# pck100clone.net
KiCad netlist of a schematic drawn in EAGLE
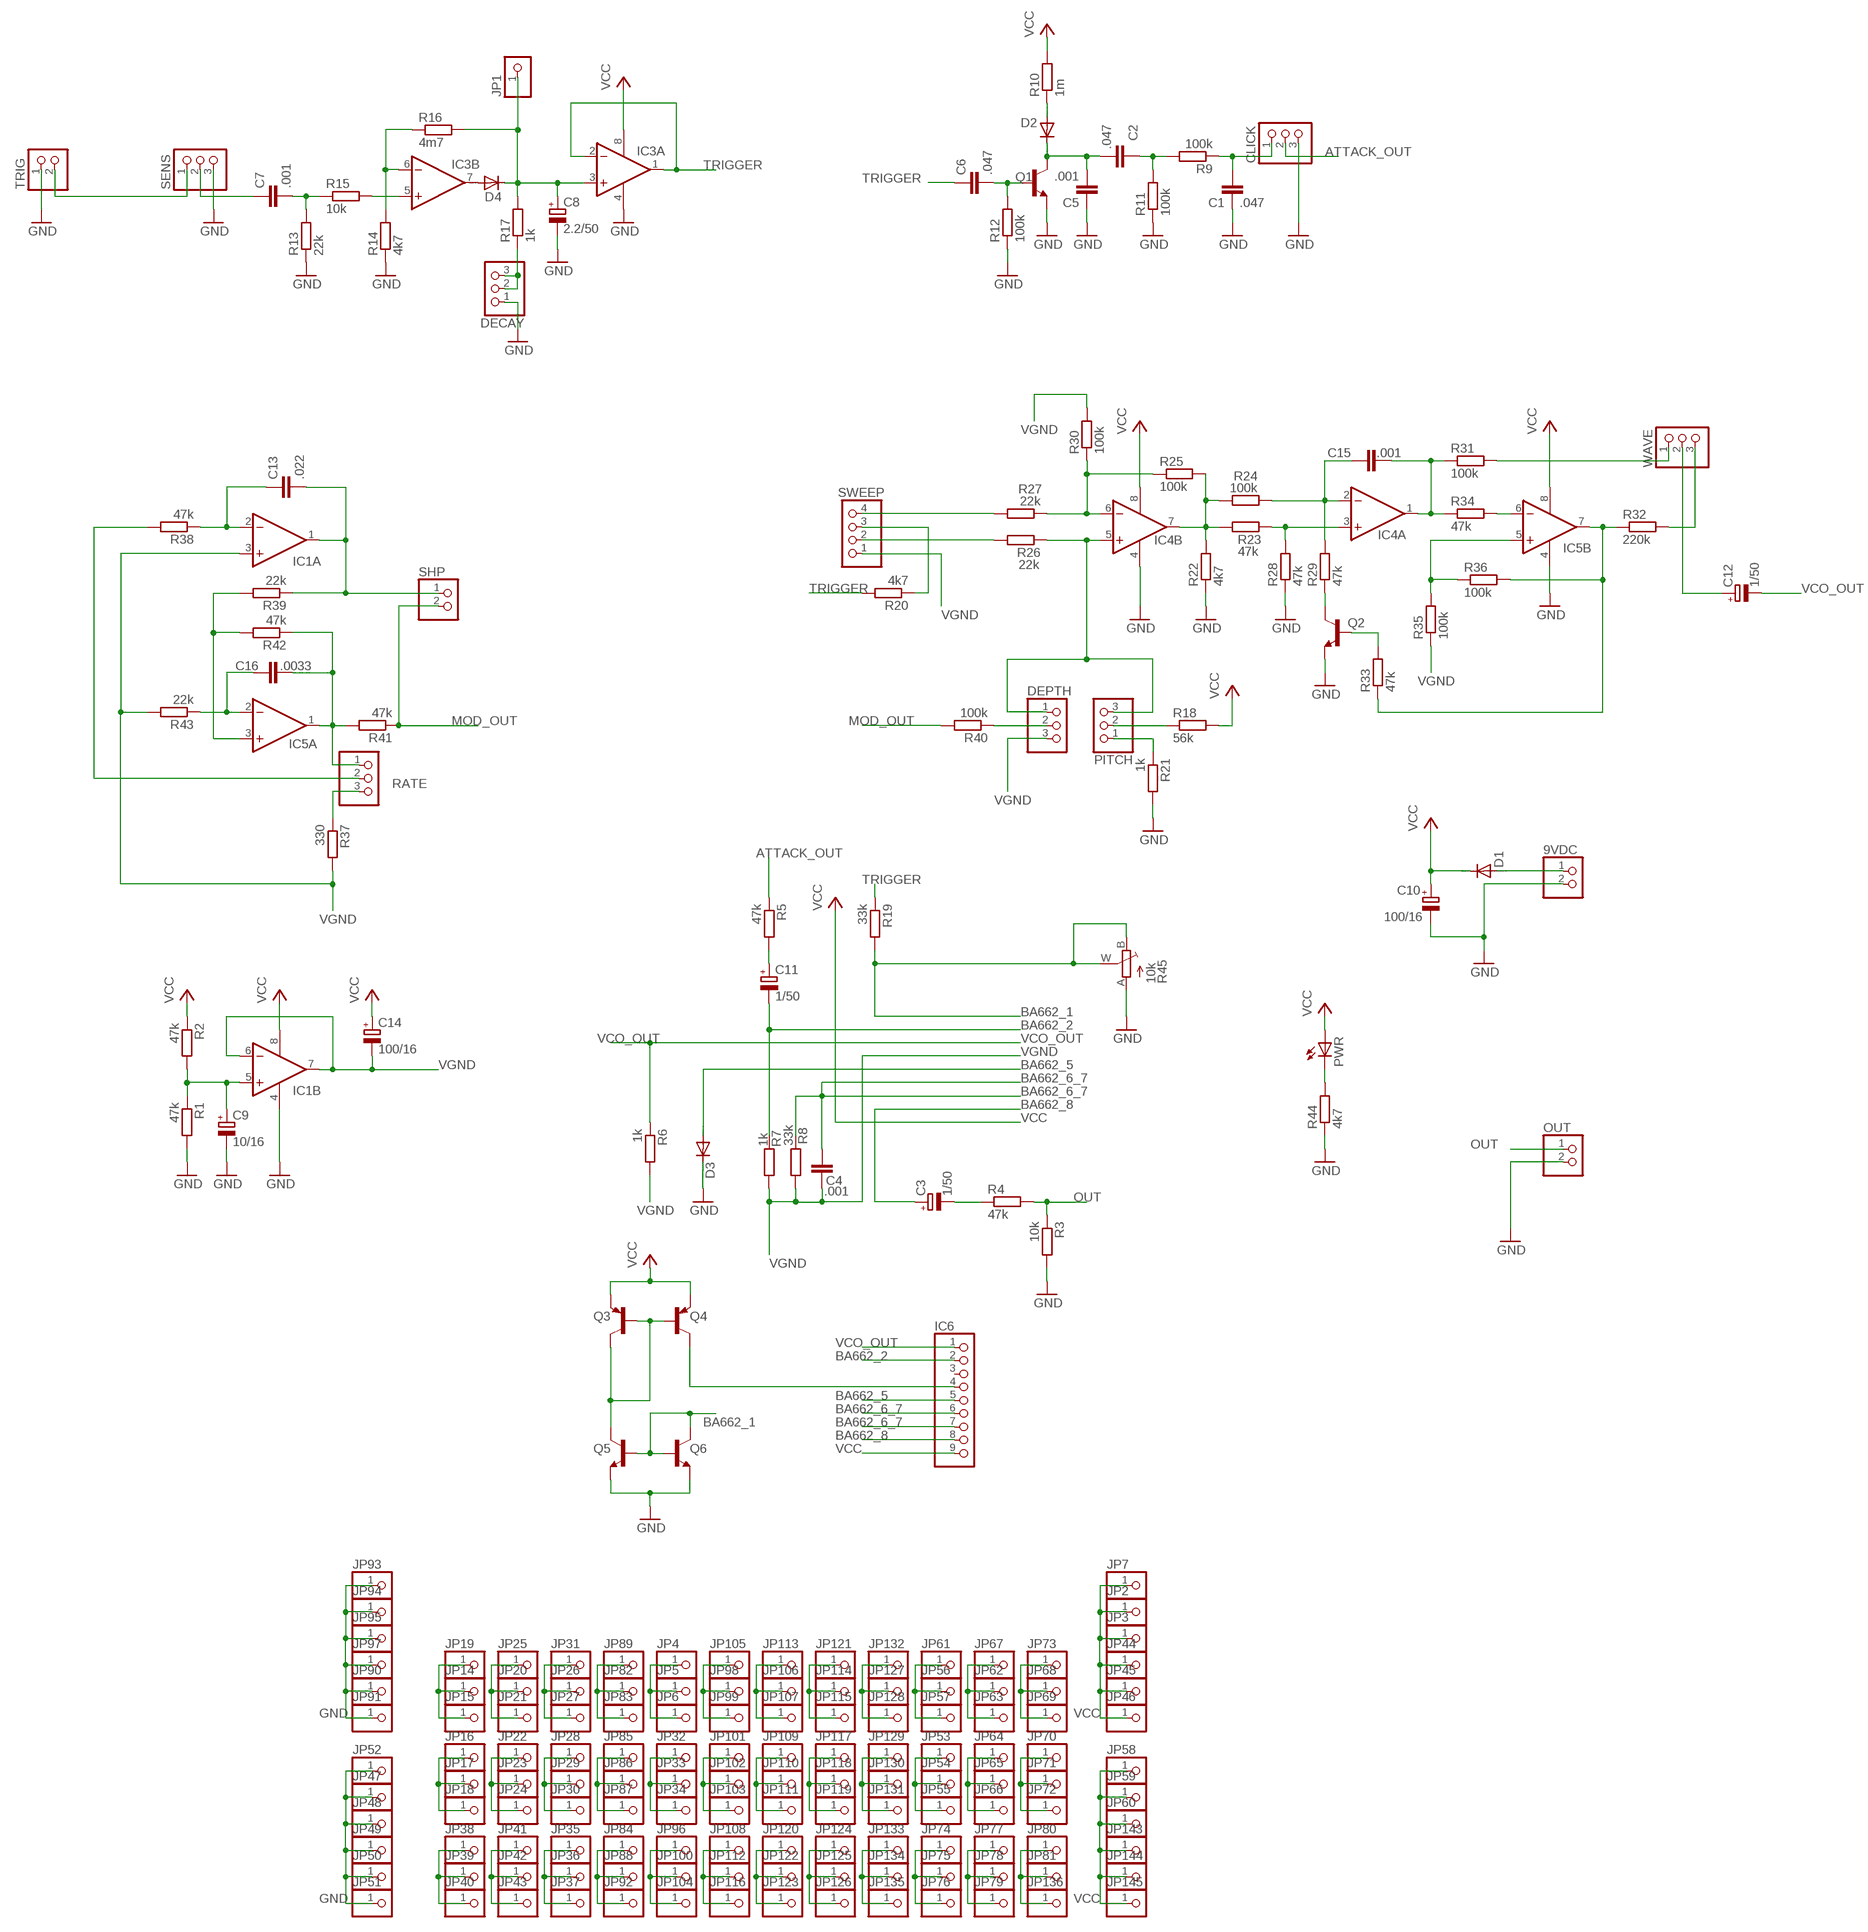
[diagram p0: schematic, sheet 1]

(export (version "E")
  (design (tool "Eeschema 10.0.6"))
  (components
    (comp (ref "9VDC")
      (value "PINHD-1X2")
      (footprint "eagle-import:1X02")
      (libsource (lib "eagle-import") (part "PINHD-1X2"))
    )
    (comp (ref "C1")
      (value ".047")
      (footprint "eagle-import:C050-025X075")
      (libsource (lib "eagle-import") (part "C-EU050-025X075"))
    )
    (comp (ref "C2")
      (value ".047")
      (footprint "eagle-import:C050-025X075")
      (libsource (lib "eagle-import") (part "C-EU050-025X075"))
    )
    (comp (ref "C3")
      (value "1/50")
      (footprint "eagle-import:E2,5-5")
      (libsource (lib "eagle-import") (part "CPOL-EUE2.5-5"))
    )
    (comp (ref "C4")
      (value ".001")
      (footprint "eagle-import:C050-025X075")
      (libsource (lib "eagle-import") (part "C-EU050-025X075"))
    )
    (comp (ref "C5")
      (value ".001")
      (footprint "eagle-import:C050-025X075")
      (libsource (lib "eagle-import") (part "C-EU050-025X075"))
    )
    (comp (ref "C6")
      (value ".047")
      (footprint "eagle-import:C050-025X075")
      (libsource (lib "eagle-import") (part "C-EU050-025X075"))
    )
    (comp (ref "C7")
      (value ".001")
      (footprint "eagle-import:C050-025X075")
      (libsource (lib "eagle-import") (part "C-EU050-025X075"))
    )
    (comp (ref "C8")
      (value "2.2/50")
      (footprint "eagle-import:E2,5-5")
      (libsource (lib "eagle-import") (part "CPOL-EUE2.5-5"))
    )
    (comp (ref "C9")
      (value "10/16")
      (footprint "eagle-import:E2,5-5")
      (libsource (lib "eagle-import") (part "CPOL-EUE2.5-5"))
    )
    (comp (ref "C10")
      (value "100/16")
      (footprint "eagle-import:E2,5-5")
      (libsource (lib "eagle-import") (part "CPOL-EUE2.5-5"))
    )
    (comp (ref "C11")
      (value "1/50")
      (footprint "eagle-import:E2,5-5")
      (libsource (lib "eagle-import") (part "CPOL-EUE2.5-5"))
    )
    (comp (ref "C12")
      (value "1/50")
      (footprint "eagle-import:E2,5-5")
      (libsource (lib "eagle-import") (part "CPOL-EUE2.5-5"))
    )
    (comp (ref "C13")
      (value ".022")
      (footprint "eagle-import:C050-025X075")
      (libsource (lib "eagle-import") (part "C-EU050-025X075"))
    )
    (comp (ref "C14")
      (value "100/16")
      (footprint "eagle-import:E2,5-5")
      (libsource (lib "eagle-import") (part "CPOL-EUE2.5-5"))
    )
    (comp (ref "C15")
      (value ".001")
      (footprint "eagle-import:C050-025X075")
      (libsource (lib "eagle-import") (part "C-EU050-025X075"))
    )
    (comp (ref "C16")
      (value ".0033")
      (footprint "eagle-import:C050-025X075")
      (libsource (lib "eagle-import") (part "C-EU050-025X075"))
    )
    (comp (ref "CLICK")
      (value "PINHD-1X3")
      (footprint "eagle-import:1X03")
      (libsource (lib "eagle-import") (part "PINHD-1X3"))
    )
    (comp (ref "D1")
      (value "1N4004")
      (footprint "eagle-import:DO41-10")
      (libsource (lib "eagle-import") (part "1N4004"))
    )
    (comp (ref "D2")
      (value "1N4148DO35-7")
      (footprint "eagle-import:DO35-7")
      (libsource (lib "eagle-import") (part "1N4148DO35-7"))
    )
    (comp (ref "D3")
      (value "1N4148DO35-7")
      (footprint "eagle-import:DO35-7")
      (libsource (lib "eagle-import") (part "1N4148DO35-7"))
    )
    (comp (ref "D4")
      (value "1N4148DO35-7")
      (footprint "eagle-import:DO35-7")
      (libsource (lib "eagle-import") (part "1N4148DO35-7"))
    )
    (comp (ref "DECAY")
      (value "PINHD-1X3")
      (footprint "eagle-import:1X03")
      (libsource (lib "eagle-import") (part "PINHD-1X3"))
    )
    (comp (ref "DEPTH")
      (value "PINHD-1X3")
      (footprint "eagle-import:1X03")
      (libsource (lib "eagle-import") (part "PINHD-1X3"))
    )
    (comp (ref "IC1")
      (value "LM358N")
      (footprint "eagle-import:DIL08")
      (libsource (lib "eagle-import") (part "LM358N"))
    )
    (comp (ref "IC3")
      (value "LM358N")
      (footprint "eagle-import:DIL08")
      (libsource (lib "eagle-import") (part "LM358N"))
    )
    (comp (ref "IC4")
      (value "LM358N")
      (footprint "eagle-import:DIL08")
      (libsource (lib "eagle-import") (part "LM358N"))
    )
    (comp (ref "IC5")
      (value "LM358N")
      (footprint "eagle-import:DIL08")
      (libsource (lib "eagle-import") (part "LM358N"))
    )
    (comp (ref "IC6")
      (value "PINHD-1X9")
      (footprint "eagle-import:1X09")
      (libsource (lib "eagle-import") (part "PINHD-1X9"))
    )
    (comp (ref "JP1")
      (value "PINHD-1X1")
      (footprint "eagle-import:1X01")
      (libsource (lib "eagle-import") (part "PINHD-1X1"))
    )
    (comp (ref "JP2")
      (value "PINHD-1X1")
      (footprint "eagle-import:1X01")
      (libsource (lib "eagle-import") (part "PINHD-1X1"))
    )
    (comp (ref "JP3")
      (value "PINHD-1X1")
      (footprint "eagle-import:1X01")
      (libsource (lib "eagle-import") (part "PINHD-1X1"))
    )
    (comp (ref "JP4")
      (value "PINHD-1X1")
      (footprint "eagle-import:1X01")
      (libsource (lib "eagle-import") (part "PINHD-1X1"))
    )
    (comp (ref "JP5")
      (value "PINHD-1X1")
      (footprint "eagle-import:1X01")
      (libsource (lib "eagle-import") (part "PINHD-1X1"))
    )
    (comp (ref "JP6")
      (value "PINHD-1X1")
      (footprint "eagle-import:1X01")
      (libsource (lib "eagle-import") (part "PINHD-1X1"))
    )
    (comp (ref "JP7")
      (value "PINHD-1X1")
      (footprint "eagle-import:1X01")
      (libsource (lib "eagle-import") (part "PINHD-1X1"))
    )
    (comp (ref "JP14")
      (value "PINHD-1X1")
      (footprint "eagle-import:1X01")
      (libsource (lib "eagle-import") (part "PINHD-1X1"))
    )
    (comp (ref "JP15")
      (value "PINHD-1X1")
      (footprint "eagle-import:1X01")
      (libsource (lib "eagle-import") (part "PINHD-1X1"))
    )
    (comp (ref "JP16")
      (value "PINHD-1X1")
      (footprint "eagle-import:1X01")
      (libsource (lib "eagle-import") (part "PINHD-1X1"))
    )
    (comp (ref "JP17")
      (value "PINHD-1X1")
      (footprint "eagle-import:1X01")
      (libsource (lib "eagle-import") (part "PINHD-1X1"))
    )
    (comp (ref "JP18")
      (value "PINHD-1X1")
      (footprint "eagle-import:1X01")
      (libsource (lib "eagle-import") (part "PINHD-1X1"))
    )
    (comp (ref "JP19")
      (value "PINHD-1X1")
      (footprint "eagle-import:1X01")
      (libsource (lib "eagle-import") (part "PINHD-1X1"))
    )
    (comp (ref "JP20")
      (value "PINHD-1X1")
      (footprint "eagle-import:1X01")
      (libsource (lib "eagle-import") (part "PINHD-1X1"))
    )
    (comp (ref "JP21")
      (value "PINHD-1X1")
      (footprint "eagle-import:1X01")
      (libsource (lib "eagle-import") (part "PINHD-1X1"))
    )
    (comp (ref "JP22")
      (value "PINHD-1X1")
      (footprint "eagle-import:1X01")
      (libsource (lib "eagle-import") (part "PINHD-1X1"))
    )
    (comp (ref "JP23")
      (value "PINHD-1X1")
      (footprint "eagle-import:1X01")
      (libsource (lib "eagle-import") (part "PINHD-1X1"))
    )
    (comp (ref "JP24")
      (value "PINHD-1X1")
      (footprint "eagle-import:1X01")
      (libsource (lib "eagle-import") (part "PINHD-1X1"))
    )
    (comp (ref "JP25")
      (value "PINHD-1X1")
      (footprint "eagle-import:1X01")
      (libsource (lib "eagle-import") (part "PINHD-1X1"))
    )
    (comp (ref "JP26")
      (value "PINHD-1X1")
      (footprint "eagle-import:1X01")
      (libsource (lib "eagle-import") (part "PINHD-1X1"))
    )
    (comp (ref "JP27")
      (value "PINHD-1X1")
      (footprint "eagle-import:1X01")
      (libsource (lib "eagle-import") (part "PINHD-1X1"))
    )
    (comp (ref "JP28")
      (value "PINHD-1X1")
      (footprint "eagle-import:1X01")
      (libsource (lib "eagle-import") (part "PINHD-1X1"))
    )
    (comp (ref "JP29")
      (value "PINHD-1X1")
      (footprint "eagle-import:1X01")
      (libsource (lib "eagle-import") (part "PINHD-1X1"))
    )
    (comp (ref "JP30")
      (value "PINHD-1X1")
      (footprint "eagle-import:1X01")
      (libsource (lib "eagle-import") (part "PINHD-1X1"))
    )
    (comp (ref "JP31")
      (value "PINHD-1X1")
      (footprint "eagle-import:1X01")
      (libsource (lib "eagle-import") (part "PINHD-1X1"))
    )
    (comp (ref "JP32")
      (value "PINHD-1X1")
      (footprint "eagle-import:1X01")
      (libsource (lib "eagle-import") (part "PINHD-1X1"))
    )
    (comp (ref "JP33")
      (value "PINHD-1X1")
      (footprint "eagle-import:1X01")
      (libsource (lib "eagle-import") (part "PINHD-1X1"))
    )
    (comp (ref "JP34")
      (value "PINHD-1X1")
      (footprint "eagle-import:1X01")
      (libsource (lib "eagle-import") (part "PINHD-1X1"))
    )
    (comp (ref "JP35")
      (value "PINHD-1X1")
      (footprint "eagle-import:1X01")
      (libsource (lib "eagle-import") (part "PINHD-1X1"))
    )
    (comp (ref "JP36")
      (value "PINHD-1X1")
      (footprint "eagle-import:1X01")
      (libsource (lib "eagle-import") (part "PINHD-1X1"))
    )
    (comp (ref "JP37")
      (value "PINHD-1X1")
      (footprint "eagle-import:1X01")
      (libsource (lib "eagle-import") (part "PINHD-1X1"))
    )
    (comp (ref "JP38")
      (value "PINHD-1X1")
      (footprint "eagle-import:1X01")
      (libsource (lib "eagle-import") (part "PINHD-1X1"))
    )
    (comp (ref "JP39")
      (value "PINHD-1X1")
      (footprint "eagle-import:1X01")
      (libsource (lib "eagle-import") (part "PINHD-1X1"))
    )
    (comp (ref "JP40")
      (value "PINHD-1X1")
      (footprint "eagle-import:1X01")
      (libsource (lib "eagle-import") (part "PINHD-1X1"))
    )
    (comp (ref "JP41")
      (value "PINHD-1X1")
      (footprint "eagle-import:1X01")
      (libsource (lib "eagle-import") (part "PINHD-1X1"))
    )
    (comp (ref "JP42")
      (value "PINHD-1X1")
      (footprint "eagle-import:1X01")
      (libsource (lib "eagle-import") (part "PINHD-1X1"))
    )
    (comp (ref "JP43")
      (value "PINHD-1X1")
      (footprint "eagle-import:1X01")
      (libsource (lib "eagle-import") (part "PINHD-1X1"))
    )
    (comp (ref "JP44")
      (value "PINHD-1X1")
      (footprint "eagle-import:1X01")
      (libsource (lib "eagle-import") (part "PINHD-1X1"))
    )
    (comp (ref "JP45")
      (value "PINHD-1X1")
      (footprint "eagle-import:1X01")
      (libsource (lib "eagle-import") (part "PINHD-1X1"))
    )
    (comp (ref "JP46")
      (value "PINHD-1X1")
      (footprint "eagle-import:1X01")
      (libsource (lib "eagle-import") (part "PINHD-1X1"))
    )
    (comp (ref "JP47")
      (value "PINHD-1X1")
      (footprint "eagle-import:1X01")
      (libsource (lib "eagle-import") (part "PINHD-1X1"))
    )
    (comp (ref "JP48")
      (value "PINHD-1X1")
      (footprint "eagle-import:1X01")
      (libsource (lib "eagle-import") (part "PINHD-1X1"))
    )
    (comp (ref "JP49")
      (value "PINHD-1X1")
      (footprint "eagle-import:1X01")
      (libsource (lib "eagle-import") (part "PINHD-1X1"))
    )
    (comp (ref "JP50")
      (value "PINHD-1X1")
      (footprint "eagle-import:1X01")
      (libsource (lib "eagle-import") (part "PINHD-1X1"))
    )
    (comp (ref "JP51")
      (value "PINHD-1X1")
      (footprint "eagle-import:1X01")
      (libsource (lib "eagle-import") (part "PINHD-1X1"))
    )
    (comp (ref "JP52")
      (value "PINHD-1X1")
      (footprint "eagle-import:1X01")
      (libsource (lib "eagle-import") (part "PINHD-1X1"))
    )
    (comp (ref "JP53")
      (value "PINHD-1X1")
      (footprint "eagle-import:1X01")
      (libsource (lib "eagle-import") (part "PINHD-1X1"))
    )
    (comp (ref "JP54")
      (value "PINHD-1X1")
      (footprint "eagle-import:1X01")
      (libsource (lib "eagle-import") (part "PINHD-1X1"))
    )
    (comp (ref "JP55")
      (value "PINHD-1X1")
      (footprint "eagle-import:1X01")
      (libsource (lib "eagle-import") (part "PINHD-1X1"))
    )
    (comp (ref "JP56")
      (value "PINHD-1X1")
      (footprint "eagle-import:1X01")
      (libsource (lib "eagle-import") (part "PINHD-1X1"))
    )
    (comp (ref "JP57")
      (value "PINHD-1X1")
      (footprint "eagle-import:1X01")
      (libsource (lib "eagle-import") (part "PINHD-1X1"))
    )
    (comp (ref "JP58")
      (value "PINHD-1X1")
      (footprint "eagle-import:1X01")
      (libsource (lib "eagle-import") (part "PINHD-1X1"))
    )
    (comp (ref "JP59")
      (value "PINHD-1X1")
      (footprint "eagle-import:1X01")
      (libsource (lib "eagle-import") (part "PINHD-1X1"))
    )
    (comp (ref "JP60")
      (value "PINHD-1X1")
      (footprint "eagle-import:1X01")
      (libsource (lib "eagle-import") (part "PINHD-1X1"))
    )
    (comp (ref "JP61")
      (value "PINHD-1X1")
      (footprint "eagle-import:1X01")
      (libsource (lib "eagle-import") (part "PINHD-1X1"))
    )
    (comp (ref "JP62")
      (value "PINHD-1X1")
      (footprint "eagle-import:1X01")
      (libsource (lib "eagle-import") (part "PINHD-1X1"))
    )
    (comp (ref "JP63")
      (value "PINHD-1X1")
      (footprint "eagle-import:1X01")
      (libsource (lib "eagle-import") (part "PINHD-1X1"))
    )
    (comp (ref "JP64")
      (value "PINHD-1X1")
      (footprint "eagle-import:1X01")
      (libsource (lib "eagle-import") (part "PINHD-1X1"))
    )
    (comp (ref "JP65")
      (value "PINHD-1X1")
      (footprint "eagle-import:1X01")
      (libsource (lib "eagle-import") (part "PINHD-1X1"))
    )
    (comp (ref "JP66")
      (value "PINHD-1X1")
      (footprint "eagle-import:1X01")
      (libsource (lib "eagle-import") (part "PINHD-1X1"))
    )
    (comp (ref "JP67")
      (value "PINHD-1X1")
      (footprint "eagle-import:1X01")
      (libsource (lib "eagle-import") (part "PINHD-1X1"))
    )
    (comp (ref "JP68")
      (value "PINHD-1X1")
      (footprint "eagle-import:1X01")
      (libsource (lib "eagle-import") (part "PINHD-1X1"))
    )
    (comp (ref "JP69")
      (value "PINHD-1X1")
      (footprint "eagle-import:1X01")
      (libsource (lib "eagle-import") (part "PINHD-1X1"))
    )
    (comp (ref "JP70")
      (value "PINHD-1X1")
      (footprint "eagle-import:1X01")
      (libsource (lib "eagle-import") (part "PINHD-1X1"))
    )
    (comp (ref "JP71")
      (value "PINHD-1X1")
      (footprint "eagle-import:1X01")
      (libsource (lib "eagle-import") (part "PINHD-1X1"))
    )
    (comp (ref "JP72")
      (value "PINHD-1X1")
      (footprint "eagle-import:1X01")
      (libsource (lib "eagle-import") (part "PINHD-1X1"))
    )
    (comp (ref "JP73")
      (value "PINHD-1X1")
      (footprint "eagle-import:1X01")
      (libsource (lib "eagle-import") (part "PINHD-1X1"))
    )
    (comp (ref "JP74")
      (value "PINHD-1X1")
      (footprint "eagle-import:1X01")
      (libsource (lib "eagle-import") (part "PINHD-1X1"))
    )
    (comp (ref "JP75")
      (value "PINHD-1X1")
      (footprint "eagle-import:1X01")
      (libsource (lib "eagle-import") (part "PINHD-1X1"))
    )
    (comp (ref "JP76")
      (value "PINHD-1X1")
      (footprint "eagle-import:1X01")
      (libsource (lib "eagle-import") (part "PINHD-1X1"))
    )
    (comp (ref "JP77")
      (value "PINHD-1X1")
      (footprint "eagle-import:1X01")
      (libsource (lib "eagle-import") (part "PINHD-1X1"))
    )
    (comp (ref "JP78")
      (value "PINHD-1X1")
      (footprint "eagle-import:1X01")
      (libsource (lib "eagle-import") (part "PINHD-1X1"))
    )
    (comp (ref "JP79")
      (value "PINHD-1X1")
      (footprint "eagle-import:1X01")
      (libsource (lib "eagle-import") (part "PINHD-1X1"))
    )
    (comp (ref "JP80")
      (value "PINHD-1X1")
      (footprint "eagle-import:1X01")
      (libsource (lib "eagle-import") (part "PINHD-1X1"))
    )
    (comp (ref "JP81")
      (value "PINHD-1X1")
      (footprint "eagle-import:1X01")
      (libsource (lib "eagle-import") (part "PINHD-1X1"))
    )
    (comp (ref "JP82")
      (value "PINHD-1X1")
      (footprint "eagle-import:1X01")
      (libsource (lib "eagle-import") (part "PINHD-1X1"))
    )
    (comp (ref "JP83")
      (value "PINHD-1X1")
      (footprint "eagle-import:1X01")
      (libsource (lib "eagle-import") (part "PINHD-1X1"))
    )
    (comp (ref "JP84")
      (value "PINHD-1X1")
      (footprint "eagle-import:1X01")
      (libsource (lib "eagle-import") (part "PINHD-1X1"))
    )
    (comp (ref "JP85")
      (value "PINHD-1X1")
      (footprint "eagle-import:1X01")
      (libsource (lib "eagle-import") (part "PINHD-1X1"))
    )
    (comp (ref "JP86")
      (value "PINHD-1X1")
      (footprint "eagle-import:1X01")
      (libsource (lib "eagle-import") (part "PINHD-1X1"))
    )
    (comp (ref "JP87")
      (value "PINHD-1X1")
      (footprint "eagle-import:1X01")
      (libsource (lib "eagle-import") (part "PINHD-1X1"))
    )
    (comp (ref "JP88")
      (value "PINHD-1X1")
      (footprint "eagle-import:1X01")
      (libsource (lib "eagle-import") (part "PINHD-1X1"))
    )
    (comp (ref "JP89")
      (value "PINHD-1X1")
      (footprint "eagle-import:1X01")
      (libsource (lib "eagle-import") (part "PINHD-1X1"))
    )
    (comp (ref "JP90")
      (value "PINHD-1X1")
      (footprint "eagle-import:1X01")
      (libsource (lib "eagle-import") (part "PINHD-1X1"))
    )
    (comp (ref "JP91")
      (value "PINHD-1X1")
      (footprint "eagle-import:1X01")
      (libsource (lib "eagle-import") (part "PINHD-1X1"))
    )
    (comp (ref "JP92")
      (value "PINHD-1X1")
      (footprint "eagle-import:1X01")
      (libsource (lib "eagle-import") (part "PINHD-1X1"))
    )
    (comp (ref "JP93")
      (value "PINHD-1X1")
      (footprint "eagle-import:1X01")
      (libsource (lib "eagle-import") (part "PINHD-1X1"))
    )
    (comp (ref "JP94")
      (value "PINHD-1X1")
      (footprint "eagle-import:1X01")
      (libsource (lib "eagle-import") (part "PINHD-1X1"))
    )
    (comp (ref "JP95")
      (value "PINHD-1X1")
      (footprint "eagle-import:1X01")
      (libsource (lib "eagle-import") (part "PINHD-1X1"))
    )
    (comp (ref "JP96")
      (value "PINHD-1X1")
      (footprint "eagle-import:1X01")
      (libsource (lib "eagle-import") (part "PINHD-1X1"))
    )
    (comp (ref "JP97")
      (value "PINHD-1X1")
      (footprint "eagle-import:1X01")
      (libsource (lib "eagle-import") (part "PINHD-1X1"))
    )
    (comp (ref "JP98")
      (value "PINHD-1X1")
      (footprint "eagle-import:1X01")
      (libsource (lib "eagle-import") (part "PINHD-1X1"))
    )
    (comp (ref "JP99")
      (value "PINHD-1X1")
      (footprint "eagle-import:1X01")
      (libsource (lib "eagle-import") (part "PINHD-1X1"))
    )
    (comp (ref "JP100")
      (value "PINHD-1X1")
      (footprint "eagle-import:1X01")
      (libsource (lib "eagle-import") (part "PINHD-1X1"))
    )
    (comp (ref "JP101")
      (value "PINHD-1X1")
      (footprint "eagle-import:1X01")
      (libsource (lib "eagle-import") (part "PINHD-1X1"))
    )
    (comp (ref "JP102")
      (value "PINHD-1X1")
      (footprint "eagle-import:1X01")
      (libsource (lib "eagle-import") (part "PINHD-1X1"))
    )
    (comp (ref "JP103")
      (value "PINHD-1X1")
      (footprint "eagle-import:1X01")
      (libsource (lib "eagle-import") (part "PINHD-1X1"))
    )
    (comp (ref "JP104")
      (value "PINHD-1X1")
      (footprint "eagle-import:1X01")
      (libsource (lib "eagle-import") (part "PINHD-1X1"))
    )
    (comp (ref "JP105")
      (value "PINHD-1X1")
      (footprint "eagle-import:1X01")
      (libsource (lib "eagle-import") (part "PINHD-1X1"))
    )
    (comp (ref "JP106")
      (value "PINHD-1X1")
      (footprint "eagle-import:1X01")
      (libsource (lib "eagle-import") (part "PINHD-1X1"))
    )
    (comp (ref "JP107")
      (value "PINHD-1X1")
      (footprint "eagle-import:1X01")
      (libsource (lib "eagle-import") (part "PINHD-1X1"))
    )
    (comp (ref "JP108")
      (value "PINHD-1X1")
      (footprint "eagle-import:1X01")
      (libsource (lib "eagle-import") (part "PINHD-1X1"))
    )
    (comp (ref "JP109")
      (value "PINHD-1X1")
      (footprint "eagle-import:1X01")
      (libsource (lib "eagle-import") (part "PINHD-1X1"))
    )
    (comp (ref "JP110")
      (value "PINHD-1X1")
      (footprint "eagle-import:1X01")
      (libsource (lib "eagle-import") (part "PINHD-1X1"))
    )
    (comp (ref "JP111")
      (value "PINHD-1X1")
      (footprint "eagle-import:1X01")
      (libsource (lib "eagle-import") (part "PINHD-1X1"))
    )
    (comp (ref "JP112")
      (value "PINHD-1X1")
      (footprint "eagle-import:1X01")
      (libsource (lib "eagle-import") (part "PINHD-1X1"))
    )
    (comp (ref "JP113")
      (value "PINHD-1X1")
      (footprint "eagle-import:1X01")
      (libsource (lib "eagle-import") (part "PINHD-1X1"))
    )
    (comp (ref "JP114")
      (value "PINHD-1X1")
      (footprint "eagle-import:1X01")
      (libsource (lib "eagle-import") (part "PINHD-1X1"))
    )
    (comp (ref "JP115")
      (value "PINHD-1X1")
      (footprint "eagle-import:1X01")
      (libsource (lib "eagle-import") (part "PINHD-1X1"))
    )
    (comp (ref "JP116")
      (value "PINHD-1X1")
      (footprint "eagle-import:1X01")
      (libsource (lib "eagle-import") (part "PINHD-1X1"))
    )
    (comp (ref "JP117")
      (value "PINHD-1X1")
      (footprint "eagle-import:1X01")
      (libsource (lib "eagle-import") (part "PINHD-1X1"))
    )
    (comp (ref "JP118")
      (value "PINHD-1X1")
      (footprint "eagle-import:1X01")
      (libsource (lib "eagle-import") (part "PINHD-1X1"))
    )
    (comp (ref "JP119")
      (value "PINHD-1X1")
      (footprint "eagle-import:1X01")
      (libsource (lib "eagle-import") (part "PINHD-1X1"))
    )
    (comp (ref "JP120")
      (value "PINHD-1X1")
      (footprint "eagle-import:1X01")
      (libsource (lib "eagle-import") (part "PINHD-1X1"))
    )
    (comp (ref "JP121")
      (value "PINHD-1X1")
      (footprint "eagle-import:1X01")
      (libsource (lib "eagle-import") (part "PINHD-1X1"))
    )
    (comp (ref "JP122")
      (value "PINHD-1X1")
      (footprint "eagle-import:1X01")
      (libsource (lib "eagle-import") (part "PINHD-1X1"))
    )
    (comp (ref "JP123")
      (value "PINHD-1X1")
      (footprint "eagle-import:1X01")
      (libsource (lib "eagle-import") (part "PINHD-1X1"))
    )
    (comp (ref "JP124")
      (value "PINHD-1X1")
      (footprint "eagle-import:1X01")
      (libsource (lib "eagle-import") (part "PINHD-1X1"))
    )
    (comp (ref "JP125")
      (value "PINHD-1X1")
      (footprint "eagle-import:1X01")
      (libsource (lib "eagle-import") (part "PINHD-1X1"))
    )
    (comp (ref "JP126")
      (value "PINHD-1X1")
      (footprint "eagle-import:1X01")
      (libsource (lib "eagle-import") (part "PINHD-1X1"))
    )
    (comp (ref "JP127")
      (value "PINHD-1X1")
      (footprint "eagle-import:1X01")
      (libsource (lib "eagle-import") (part "PINHD-1X1"))
    )
    (comp (ref "JP128")
      (value "PINHD-1X1")
      (footprint "eagle-import:1X01")
      (libsource (lib "eagle-import") (part "PINHD-1X1"))
    )
    (comp (ref "JP129")
      (value "PINHD-1X1")
      (footprint "eagle-import:1X01")
      (libsource (lib "eagle-import") (part "PINHD-1X1"))
    )
    (comp (ref "JP130")
      (value "PINHD-1X1")
      (footprint "eagle-import:1X01")
      (libsource (lib "eagle-import") (part "PINHD-1X1"))
    )
    (comp (ref "JP131")
      (value "PINHD-1X1")
      (footprint "eagle-import:1X01")
      (libsource (lib "eagle-import") (part "PINHD-1X1"))
    )
    (comp (ref "JP132")
      (value "PINHD-1X1")
      (footprint "eagle-import:1X01")
      (libsource (lib "eagle-import") (part "PINHD-1X1"))
    )
    (comp (ref "JP133")
      (value "PINHD-1X1")
      (footprint "eagle-import:1X01")
      (libsource (lib "eagle-import") (part "PINHD-1X1"))
    )
    (comp (ref "JP134")
      (value "PINHD-1X1")
      (footprint "eagle-import:1X01")
      (libsource (lib "eagle-import") (part "PINHD-1X1"))
    )
    (comp (ref "JP135")
      (value "PINHD-1X1")
      (footprint "eagle-import:1X01")
      (libsource (lib "eagle-import") (part "PINHD-1X1"))
    )
    (comp (ref "JP136")
      (value "PINHD-1X1")
      (footprint "eagle-import:1X01")
      (libsource (lib "eagle-import") (part "PINHD-1X1"))
    )
    (comp (ref "JP143")
      (value "PINHD-1X1")
      (footprint "eagle-import:1X01")
      (libsource (lib "eagle-import") (part "PINHD-1X1"))
    )
    (comp (ref "JP144")
      (value "PINHD-1X1")
      (footprint "eagle-import:1X01")
      (libsource (lib "eagle-import") (part "PINHD-1X1"))
    )
    (comp (ref "JP145")
      (value "PINHD-1X1")
      (footprint "eagle-import:1X01")
      (libsource (lib "eagle-import") (part "PINHD-1X1"))
    )
    (comp (ref "OUT")
      (value "PINHD-1X2")
      (footprint "eagle-import:1X02")
      (libsource (lib "eagle-import") (part "PINHD-1X2"))
    )
    (comp (ref "PITCH")
      (value "PINHD-1X3")
      (footprint "eagle-import:1X03")
      (libsource (lib "eagle-import") (part "PINHD-1X3"))
    )
    (comp (ref "PWR")
      (value "LED3MM")
      (footprint "eagle-import:LED3MM")
      (libsource (lib "eagle-import") (part "LED3MM"))
    )
    (comp (ref "Q1")
      (value "2SC945")
      (footprint "eagle-import:TO92-ECB")
      (libsource (lib "eagle-import") (part "2SC945"))
    )
    (comp (ref "Q2")
      (value "2SC945")
      (footprint "eagle-import:TO92-ECB")
      (libsource (lib "eagle-import") (part "2SC945"))
    )
    (comp (ref "Q3")
      (value "2N3906")
      (footprint "eagle-import:TO92")
      (libsource (lib "eagle-import") (part "2N3906"))
    )
    (comp (ref "Q4")
      (value "2N3906")
      (footprint "eagle-import:TO92")
      (libsource (lib "eagle-import") (part "2N3906"))
    )
    (comp (ref "Q5")
      (value "2N3904")
      (footprint "eagle-import:TO92")
      (libsource (lib "eagle-import") (part "2N3904"))
    )
    (comp (ref "Q6")
      (value "2N3904")
      (footprint "eagle-import:TO92")
      (libsource (lib "eagle-import") (part "2N3904"))
    )
    (comp (ref "R1")
      (value "47k")
      (footprint "eagle-import:0207_7")
      (libsource (lib "eagle-import") (part "R-EU_0207/7"))
    )
    (comp (ref "R2")
      (value "47k")
      (footprint "eagle-import:0207_7")
      (libsource (lib "eagle-import") (part "R-EU_0207/7"))
    )
    (comp (ref "R3")
      (value "10k")
      (footprint "eagle-import:0207_7")
      (libsource (lib "eagle-import") (part "R-EU_0207/7"))
    )
    (comp (ref "R4")
      (value "47k")
      (footprint "eagle-import:0207_7")
      (libsource (lib "eagle-import") (part "R-EU_0207/7"))
    )
    (comp (ref "R5")
      (value "47k")
      (footprint "eagle-import:0207_7")
      (libsource (lib "eagle-import") (part "R-EU_0207/7"))
    )
    (comp (ref "R6")
      (value "1k")
      (footprint "eagle-import:0207_7")
      (libsource (lib "eagle-import") (part "R-EU_0207/7"))
    )
    (comp (ref "R7")
      (value "1k")
      (footprint "eagle-import:0207_7")
      (libsource (lib "eagle-import") (part "R-EU_0207/7"))
    )
    (comp (ref "R8")
      (value "33k")
      (footprint "eagle-import:0207_7")
      (libsource (lib "eagle-import") (part "R-EU_0207/7"))
    )
    (comp (ref "R9")
      (value "100k")
      (footprint "eagle-import:0207_7")
      (libsource (lib "eagle-import") (part "R-EU_0207/7"))
    )
    (comp (ref "R10")
      (value "1m")
      (footprint "eagle-import:0207_7")
      (libsource (lib "eagle-import") (part "R-EU_0207/7"))
    )
    (comp (ref "R11")
      (value "100k")
      (footprint "eagle-import:0207_7")
      (libsource (lib "eagle-import") (part "R-EU_0207/7"))
    )
    (comp (ref "R12")
      (value "100k")
      (footprint "eagle-import:0207_7")
      (libsource (lib "eagle-import") (part "R-EU_0207/7"))
    )
    (comp (ref "R13")
      (value "22k")
      (footprint "eagle-import:0207_7")
      (libsource (lib "eagle-import") (part "R-EU_0207/7"))
    )
    (comp (ref "R14")
      (value "4k7")
      (footprint "eagle-import:0207_7")
      (libsource (lib "eagle-import") (part "R-EU_0207/7"))
    )
    (comp (ref "R15")
      (value "10k")
      (footprint "eagle-import:0207_7")
      (libsource (lib "eagle-import") (part "R-EU_0207/7"))
    )
    (comp (ref "R16")
      (value "4m7")
      (footprint "eagle-import:0207_7")
      (libsource (lib "eagle-import") (part "R-EU_0207/7"))
    )
    (comp (ref "R17")
      (value "1k")
      (footprint "eagle-import:0207_7")
      (libsource (lib "eagle-import") (part "R-EU_0207/7"))
    )
    (comp (ref "R18")
      (value "56k")
      (footprint "eagle-import:0207_7")
      (libsource (lib "eagle-import") (part "R-EU_0207/7"))
    )
    (comp (ref "R19")
      (value "33k")
      (footprint "eagle-import:0207_7")
      (libsource (lib "eagle-import") (part "R-EU_0207/7"))
    )
    (comp (ref "R20")
      (value "4k7")
      (footprint "eagle-import:0207_7")
      (libsource (lib "eagle-import") (part "R-EU_0207/7"))
    )
    (comp (ref "R21")
      (value "1k")
      (footprint "eagle-import:0207_7")
      (libsource (lib "eagle-import") (part "R-EU_0207/7"))
    )
    (comp (ref "R22")
      (value "4k7")
      (footprint "eagle-import:0207_7")
      (libsource (lib "eagle-import") (part "R-EU_0207/7"))
    )
    (comp (ref "R23")
      (value "47k")
      (footprint "eagle-import:0207_7")
      (libsource (lib "eagle-import") (part "R-EU_0207/7"))
    )
    (comp (ref "R24")
      (value "100k")
      (footprint "eagle-import:0207_7")
      (libsource (lib "eagle-import") (part "R-EU_0207/7"))
    )
    (comp (ref "R25")
      (value "100k")
      (footprint "eagle-import:0207_7")
      (libsource (lib "eagle-import") (part "R-EU_0207/7"))
    )
    (comp (ref "R26")
      (value "22k")
      (footprint "eagle-import:0207_7")
      (libsource (lib "eagle-import") (part "R-EU_0207/7"))
    )
    (comp (ref "R27")
      (value "22k")
      (footprint "eagle-import:0207_7")
      (libsource (lib "eagle-import") (part "R-EU_0207/7"))
    )
    (comp (ref "R28")
      (value "47k")
      (footprint "eagle-import:0207_7")
      (libsource (lib "eagle-import") (part "R-EU_0207/7"))
    )
    (comp (ref "R29")
      (value "47k")
      (footprint "eagle-import:0207_7")
      (libsource (lib "eagle-import") (part "R-EU_0207/7"))
    )
    (comp (ref "R30")
      (value "100k")
      (footprint "eagle-import:0207_7")
      (libsource (lib "eagle-import") (part "R-EU_0207/7"))
    )
    (comp (ref "R31")
      (value "100k")
      (footprint "eagle-import:0207_7")
      (libsource (lib "eagle-import") (part "R-EU_0207/7"))
    )
    (comp (ref "R32")
      (value "220k")
      (footprint "eagle-import:0207_7")
      (libsource (lib "eagle-import") (part "R-EU_0207/7"))
    )
    (comp (ref "R33")
      (value "47k")
      (footprint "eagle-import:0207_7")
      (libsource (lib "eagle-import") (part "R-EU_0207/7"))
    )
    (comp (ref "R34")
      (value "47k")
      (footprint "eagle-import:0207_7")
      (libsource (lib "eagle-import") (part "R-EU_0207/7"))
    )
    (comp (ref "R35")
      (value "100k")
      (footprint "eagle-import:0207_7")
      (libsource (lib "eagle-import") (part "R-EU_0207/7"))
    )
    (comp (ref "R36")
      (value "100k")
      (footprint "eagle-import:0207_7")
      (libsource (lib "eagle-import") (part "R-EU_0207/7"))
    )
    (comp (ref "R37")
      (value "330")
      (footprint "eagle-import:0207_7")
      (libsource (lib "eagle-import") (part "R-EU_0207/7"))
    )
    (comp (ref "R38")
      (value "47k")
      (footprint "eagle-import:0207_7")
      (libsource (lib "eagle-import") (part "R-EU_0207/7"))
    )
    (comp (ref "R39")
      (value "22k")
      (footprint "eagle-import:0207_7")
      (libsource (lib "eagle-import") (part "R-EU_0207/7"))
    )
    (comp (ref "R40")
      (value "100k")
      (footprint "eagle-import:0207_7")
      (libsource (lib "eagle-import") (part "R-EU_0207/7"))
    )
    (comp (ref "R41")
      (value "47k")
      (footprint "eagle-import:0207_7")
      (libsource (lib "eagle-import") (part "R-EU_0207/7"))
    )
    (comp (ref "R42")
      (value "47k")
      (footprint "eagle-import:0207_7")
      (libsource (lib "eagle-import") (part "R-EU_0207/7"))
    )
    (comp (ref "R43")
      (value "22k")
      (footprint "eagle-import:0207_7")
      (libsource (lib "eagle-import") (part "R-EU_0207/7"))
    )
    (comp (ref "R44")
      (value "4k7")
      (footprint "eagle-import:0207_7")
      (libsource (lib "eagle-import") (part "R-EU_0207/7"))
    )
    (comp (ref "R45")
      (value "10k")
      (footprint "eagle-import:TRIM-N")
      (libsource (lib "eagle-import") (part "TRIM_EU-"))
    )
    (comp (ref "RATE")
      (value "PINHD-1X3")
      (footprint "eagle-import:1X03")
      (libsource (lib "eagle-import") (part "PINHD-1X3"))
    )
    (comp (ref "SENS")
      (value "PINHD-1X3")
      (footprint "eagle-import:1X03")
      (libsource (lib "eagle-import") (part "PINHD-1X3"))
    )
    (comp (ref "SHP")
      (value "PINHD-1X2")
      (footprint "eagle-import:1X02")
      (libsource (lib "eagle-import") (part "PINHD-1X2"))
    )
    (comp (ref "SWEEP")
      (value "PINHD-1X4")
      (footprint "eagle-import:1X04")
      (libsource (lib "eagle-import") (part "PINHD-1X4"))
    )
    (comp (ref "TRIG")
      (value "PINHD-1X2")
      (footprint "eagle-import:1X02")
      (libsource (lib "eagle-import") (part "PINHD-1X2"))
    )
    (comp (ref "WAVE")
      (value "PINHD-1X3")
      (footprint "eagle-import:1X03")
      (libsource (lib "eagle-import") (part "PINHD-1X3"))
    )
  )
  (nets
    (net (code "1") (name "/ATTACK_OUT") (class "Default")
      (node (ref "CLICK") (pin "2") (pinfunction "2_2") (pintype "passive"))
      (node (ref "R5") (pin "1") (pinfunction "1_1") (pintype "passive"))
    )
    (net (code "2") (name "/BA662_1") (class "Default")
      (node (ref "Q5") (pin "2") (pinfunction "B_2") (pintype "passive"))
      (node (ref "Q6") (pin "1") (pinfunction "C_1") (pintype "passive"))
      (node (ref "Q6") (pin "2") (pinfunction "B_2") (pintype "passive"))
      (node (ref "R19") (pin "2") (pinfunction "2_2") (pintype "passive"))
      (node (ref "R45") (pin "B") (pinfunction "E_B") (pintype "passive"))
      (node (ref "R45") (pin "W") (pinfunction "S_W") (pintype "passive"))
    )
    (net (code "3") (name "/BA662_2") (class "Default")
      (node (ref "C11") (pin "-") (pinfunction "-_-") (pintype "passive"))
      (node (ref "IC6") (pin "2") (pinfunction "2_2") (pintype "passive"))
      (node (ref "R7") (pin "1") (pinfunction "1_1") (pintype "passive"))
    )
    (net (code "4") (name "/BA662_5") (class "Default")
      (node (ref "D3") (pin "A") (pinfunction "A_A") (pintype "passive"))
      (node (ref "IC6") (pin "5") (pinfunction "5_5") (pintype "passive"))
    )
    (net (code "5") (name "/BA662_6_7") (class "Default")
      (node (ref "C4") (pin "2") (pinfunction "2_2") (pintype "passive"))
      (node (ref "IC6") (pin "6") (pinfunction "6_6") (pintype "passive"))
      (node (ref "IC6") (pin "7") (pinfunction "7_7") (pintype "passive"))
      (node (ref "R8") (pin "1") (pinfunction "1_1") (pintype "passive"))
    )
    (net (code "6") (name "/BA662_8") (class "Default")
      (node (ref "C3") (pin "+") (pinfunction "+_+") (pintype "passive"))
      (node (ref "IC6") (pin "8") (pinfunction "8_8") (pintype "passive"))
    )
    (net (code "7") (name "/MOD_OUT") (class "Default")
      (node (ref "R40") (pin "2") (pinfunction "2_2") (pintype "passive"))
      (node (ref "R41") (pin "1") (pinfunction "1_1") (pintype "passive"))
      (node (ref "SHP") (pin "2") (pinfunction "2_2") (pintype "passive"))
    )
    (net (code "8") (name "/OUT") (class "Default")
      (node (ref "OUT") (pin "1") (pinfunction "1_1") (pintype "passive"))
      (node (ref "R3") (pin "1") (pinfunction "1_1") (pintype "passive"))
      (node (ref "R4") (pin "2") (pinfunction "2_2") (pintype "passive"))
    )
    (net (code "9") (name "/TRIGGER") (class "Default")
      (node (ref "C6") (pin "1") (pinfunction "1_1") (pintype "passive"))
      (node (ref "IC3") (pin "1") (pinfunction "OUT_1") (pintype "output"))
      (node (ref "IC3") (pin "2") (pinfunction "-IN_2") (pintype "input"))
      (node (ref "R19") (pin "1") (pinfunction "1_1") (pintype "passive"))
      (node (ref "R20") (pin "2") (pinfunction "2_2") (pintype "passive"))
    )
    (net (code "10") (name "/VCO_OUT") (class "Default")
      (node (ref "C12") (pin "-") (pinfunction "-_-") (pintype "passive"))
      (node (ref "IC6") (pin "1") (pinfunction "1_1") (pintype "passive"))
      (node (ref "R6") (pin "1") (pinfunction "1_1") (pintype "passive"))
    )
    (net (code "11") (name "/VGND") (class "Default")
      (node (ref "C14") (pin "-") (pinfunction "-_-") (pintype "passive"))
      (node (ref "C4") (pin "1") (pinfunction "1_1") (pintype "passive"))
      (node (ref "DEPTH") (pin "3") (pinfunction "3_3") (pintype "passive"))
      (node (ref "IC1") (pin "3") (pinfunction "+IN_3") (pintype "input"))
      (node (ref "IC1") (pin "6") (pinfunction "-IN_6") (pintype "input"))
      (node (ref "IC1") (pin "7") (pinfunction "OUT_7") (pintype "output"))
      (node (ref "R30") (pin "2") (pinfunction "2_2") (pintype "passive"))
      (node (ref "R35") (pin "1") (pinfunction "1_1") (pintype "passive"))
      (node (ref "R37") (pin "2") (pinfunction "2_2") (pintype "passive"))
      (node (ref "R43") (pin "2") (pinfunction "2_2") (pintype "passive"))
      (node (ref "R6") (pin "2") (pinfunction "2_2") (pintype "passive"))
      (node (ref "R7") (pin "2") (pinfunction "2_2") (pintype "passive"))
      (node (ref "R8") (pin "2") (pinfunction "2_2") (pintype "passive"))
      (node (ref "SWEEP") (pin "1") (pinfunction "1_1") (pintype "passive"))
    )
    (net (code "12") (name "GND") (class "Default")
      (node (ref "9VDC") (pin "2") (pinfunction "2_2") (pintype "passive"))
      (node (ref "C1") (pin "1") (pinfunction "1_1") (pintype "passive"))
      (node (ref "C10") (pin "-") (pinfunction "-_-") (pintype "passive"))
      (node (ref "C5") (pin "1") (pinfunction "1_1") (pintype "passive"))
      (node (ref "C8") (pin "-") (pinfunction "-_-") (pintype "passive"))
      (node (ref "C9") (pin "-") (pinfunction "-_-") (pintype "passive"))
      (node (ref "CLICK") (pin "3") (pinfunction "3_3") (pintype "passive"))
      (node (ref "D3") (pin "C") (pinfunction "C_C") (pintype "passive"))
      (node (ref "DECAY") (pin "1") (pinfunction "1_1") (pintype "passive"))
      (node (ref "IC1") (pin "4") (pinfunction "V-_4") (pintype "power_in"))
      (node (ref "IC3") (pin "4") (pinfunction "V-_4") (pintype "power_in"))
      (node (ref "IC4") (pin "4") (pinfunction "V-_4") (pintype "power_in"))
      (node (ref "IC5") (pin "4") (pinfunction "V-_4") (pintype "power_in"))
      (node (ref "JP47") (pin "1") (pinfunction "1_1") (pintype "passive"))
      (node (ref "JP48") (pin "1") (pinfunction "1_1") (pintype "passive"))
      (node (ref "JP49") (pin "1") (pinfunction "1_1") (pintype "passive"))
      (node (ref "JP50") (pin "1") (pinfunction "1_1") (pintype "passive"))
      (node (ref "JP51") (pin "1") (pinfunction "1_1") (pintype "passive"))
      (node (ref "JP52") (pin "1") (pinfunction "1_1") (pintype "passive"))
      (node (ref "JP90") (pin "1") (pinfunction "1_1") (pintype "passive"))
      (node (ref "JP91") (pin "1") (pinfunction "1_1") (pintype "passive"))
      (node (ref "JP93") (pin "1") (pinfunction "1_1") (pintype "passive"))
      (node (ref "JP94") (pin "1") (pinfunction "1_1") (pintype "passive"))
      (node (ref "JP95") (pin "1") (pinfunction "1_1") (pintype "passive"))
      (node (ref "JP97") (pin "1") (pinfunction "1_1") (pintype "passive"))
      (node (ref "OUT") (pin "2") (pinfunction "2_2") (pintype "passive"))
      (node (ref "Q1") (pin "E") (pinfunction "E_E") (pintype "passive"))
      (node (ref "Q2") (pin "E") (pinfunction "E_E") (pintype "passive"))
      (node (ref "Q5") (pin "3") (pinfunction "E_3") (pintype "passive"))
      (node (ref "Q6") (pin "3") (pinfunction "E_3") (pintype "passive"))
      (node (ref "R1") (pin "2") (pinfunction "2_2") (pintype "passive"))
      (node (ref "R11") (pin "1") (pinfunction "1_1") (pintype "passive"))
      (node (ref "R12") (pin "1") (pinfunction "1_1") (pintype "passive"))
      (node (ref "R13") (pin "1") (pinfunction "1_1") (pintype "passive"))
      (node (ref "R14") (pin "1") (pinfunction "1_1") (pintype "passive"))
      (node (ref "R21") (pin "2") (pinfunction "2_2") (pintype "passive"))
      (node (ref "R22") (pin "1") (pinfunction "1_1") (pintype "passive"))
      (node (ref "R28") (pin "1") (pinfunction "1_1") (pintype "passive"))
      (node (ref "R3") (pin "2") (pinfunction "2_2") (pintype "passive"))
      (node (ref "R44") (pin "1") (pinfunction "1_1") (pintype "passive"))
      (node (ref "R45") (pin "A") (pinfunction "A_A") (pintype "passive"))
      (node (ref "SENS") (pin "3") (pinfunction "3_3") (pintype "passive"))
      (node (ref "TRIG") (pin "1") (pinfunction "1_1") (pintype "passive"))
    )
    (net (code "13") (name "Net-(9VDC-Pad1)") (class "Default")
      (node (ref "9VDC") (pin "1") (pinfunction "1_1") (pintype "passive"))
      (node (ref "D1") (pin "A") (pinfunction "A_A") (pintype "passive"))
    )
    (net (code "14") (name "Net-(C1-Pad2)") (class "Default")
      (node (ref "C1") (pin "2") (pinfunction "2_2") (pintype "passive"))
      (node (ref "CLICK") (pin "1") (pinfunction "1_1") (pintype "passive"))
      (node (ref "R9") (pin "1") (pinfunction "1_1") (pintype "passive"))
    )
    (net (code "15") (name "Net-(C2-Pad1)") (class "Default")
      (node (ref "C2") (pin "1") (pinfunction "1_1") (pintype "passive"))
      (node (ref "R11") (pin "2") (pinfunction "2_2") (pintype "passive"))
      (node (ref "R9") (pin "2") (pinfunction "2_2") (pintype "passive"))
    )
    (net (code "16") (name "Net-(C2-Pad2)") (class "Default")
      (node (ref "C2") (pin "2") (pinfunction "2_2") (pintype "passive"))
      (node (ref "C5") (pin "2") (pinfunction "2_2") (pintype "passive"))
      (node (ref "D2") (pin "C") (pinfunction "C_C") (pintype "passive"))
      (node (ref "Q1") (pin "C") (pinfunction "C_C") (pintype "passive"))
    )
    (net (code "17") (name "Net-(C3-Pad-)") (class "Default")
      (node (ref "C3") (pin "-") (pinfunction "-_-") (pintype "passive"))
      (node (ref "R4") (pin "1") (pinfunction "1_1") (pintype "passive"))
    )
    (net (code "18") (name "Net-(C6-Pad2)") (class "Default")
      (node (ref "C6") (pin "2") (pinfunction "2_2") (pintype "passive"))
      (node (ref "Q1") (pin "B") (pinfunction "B_B") (pintype "passive"))
      (node (ref "R12") (pin "2") (pinfunction "2_2") (pintype "passive"))
    )
    (net (code "19") (name "Net-(C7-Pad1)") (class "Default")
      (node (ref "C7") (pin "1") (pinfunction "1_1") (pintype "passive"))
      (node (ref "SENS") (pin "2") (pinfunction "2_2") (pintype "passive"))
    )
    (net (code "20") (name "Net-(C7-Pad2)") (class "Default")
      (node (ref "C7") (pin "2") (pinfunction "2_2") (pintype "passive"))
      (node (ref "R13") (pin "2") (pinfunction "2_2") (pintype "passive"))
      (node (ref "R15") (pin "1") (pinfunction "1_1") (pintype "passive"))
    )
    (net (code "21") (name "Net-(C11-Pad+)") (class "Default")
      (node (ref "C11") (pin "+") (pinfunction "+_+") (pintype "passive"))
      (node (ref "R5") (pin "2") (pinfunction "2_2") (pintype "passive"))
    )
    (net (code "22") (name "Net-(C12-Pad+)") (class "Default")
      (node (ref "C12") (pin "+") (pinfunction "+_+") (pintype "passive"))
      (node (ref "WAVE") (pin "2") (pinfunction "2_2") (pintype "passive"))
    )
    (net (code "23") (name "Net-(D2-PadA)") (class "Default")
      (node (ref "D2") (pin "A") (pinfunction "A_A") (pintype "passive"))
      (node (ref "R10") (pin "1") (pinfunction "1_1") (pintype "passive"))
    )
    (net (code "24") (name "Net-(DECAY-Pad2)") (class "Default")
      (node (ref "DECAY") (pin "2") (pinfunction "2_2") (pintype "passive"))
      (node (ref "DECAY") (pin "3") (pinfunction "3_3") (pintype "passive"))
      (node (ref "R17") (pin "1") (pinfunction "1_1") (pintype "passive"))
    )
    (net (code "25") (name "Net-(DEPTH-Pad2)") (class "Default")
      (node (ref "DEPTH") (pin "2") (pinfunction "2_2") (pintype "passive"))
      (node (ref "R40") (pin "1") (pinfunction "1_1") (pintype "passive"))
    )
    (net (code "26") (name "Net-(IC1A--IN)") (class "Default")
      (node (ref "C13") (pin "1") (pinfunction "1_1") (pintype "passive"))
      (node (ref "IC1") (pin "2") (pinfunction "-IN_2") (pintype "input"))
      (node (ref "R38") (pin "1") (pinfunction "1_1") (pintype "passive"))
    )
    (net (code "27") (name "Net-(IC1A-OUT)") (class "Default")
      (node (ref "C13") (pin "2") (pinfunction "2_2") (pintype "passive"))
      (node (ref "IC1") (pin "1") (pinfunction "OUT_1") (pintype "output"))
      (node (ref "R39") (pin "1") (pinfunction "1_1") (pintype "passive"))
      (node (ref "SHP") (pin "1") (pinfunction "1_1") (pintype "passive"))
    )
    (net (code "28") (name "Net-(IC1B-+IN)") (class "Default")
      (node (ref "C9") (pin "+") (pinfunction "+_+") (pintype "passive"))
      (node (ref "IC1") (pin "5") (pinfunction "+IN_5") (pintype "input"))
      (node (ref "R1") (pin "1") (pinfunction "1_1") (pintype "passive"))
      (node (ref "R2") (pin "2") (pinfunction "2_2") (pintype "passive"))
    )
    (net (code "29") (name "Net-(IC3A-+IN)") (class "Default")
      (node (ref "C8") (pin "+") (pinfunction "+_+") (pintype "passive"))
      (node (ref "D4") (pin "C") (pinfunction "C_C") (pintype "passive"))
      (node (ref "IC3") (pin "3") (pinfunction "+IN_3") (pintype "input"))
      (node (ref "JP1") (pin "1") (pinfunction "1_1") (pintype "passive"))
      (node (ref "R16") (pin "2") (pinfunction "2_2") (pintype "passive"))
      (node (ref "R17") (pin "2") (pinfunction "2_2") (pintype "passive"))
    )
    (net (code "30") (name "Net-(IC3B-+IN)") (class "Default")
      (node (ref "IC3") (pin "5") (pinfunction "+IN_5") (pintype "input"))
      (node (ref "R15") (pin "2") (pinfunction "2_2") (pintype "passive"))
    )
    (net (code "31") (name "Net-(IC3B--IN)") (class "Default")
      (node (ref "IC3") (pin "6") (pinfunction "-IN_6") (pintype "input"))
      (node (ref "R14") (pin "2") (pinfunction "2_2") (pintype "passive"))
      (node (ref "R16") (pin "1") (pinfunction "1_1") (pintype "passive"))
    )
    (net (code "32") (name "Net-(IC3B-OUT)") (class "Default")
      (node (ref "D4") (pin "A") (pinfunction "A_A") (pintype "passive"))
      (node (ref "IC3") (pin "7") (pinfunction "OUT_7") (pintype "output"))
    )
    (net (code "33") (name "Net-(IC4A-+IN)") (class "Default")
      (node (ref "IC4") (pin "3") (pinfunction "+IN_3") (pintype "input"))
      (node (ref "R23") (pin "2") (pinfunction "2_2") (pintype "passive"))
      (node (ref "R28") (pin "2") (pinfunction "2_2") (pintype "passive"))
    )
    (net (code "34") (name "Net-(IC4A--IN)") (class "Default")
      (node (ref "C15") (pin "2") (pinfunction "2_2") (pintype "passive"))
      (node (ref "IC4") (pin "2") (pinfunction "-IN_2") (pintype "input"))
      (node (ref "R24") (pin "2") (pinfunction "2_2") (pintype "passive"))
      (node (ref "R29") (pin "2") (pinfunction "2_2") (pintype "passive"))
    )
    (net (code "35") (name "Net-(IC4A-OUT)") (class "Default")
      (node (ref "C15") (pin "1") (pinfunction "1_1") (pintype "passive"))
      (node (ref "IC4") (pin "1") (pinfunction "OUT_1") (pintype "output"))
      (node (ref "R31") (pin "1") (pinfunction "1_1") (pintype "passive"))
      (node (ref "R34") (pin "1") (pinfunction "1_1") (pintype "passive"))
    )
    (net (code "36") (name "Net-(IC4B-+IN)") (class "Default")
      (node (ref "DEPTH") (pin "1") (pinfunction "1_1") (pintype "passive"))
      (node (ref "IC4") (pin "5") (pinfunction "+IN_5") (pintype "input"))
      (node (ref "PITCH") (pin "3") (pinfunction "3_3") (pintype "passive"))
      (node (ref "R26") (pin "1") (pinfunction "1_1") (pintype "passive"))
    )
    (net (code "37") (name "Net-(IC4B--IN)") (class "Default")
      (node (ref "IC4") (pin "6") (pinfunction "-IN_6") (pintype "input"))
      (node (ref "R25") (pin "1") (pinfunction "1_1") (pintype "passive"))
      (node (ref "R27") (pin "1") (pinfunction "1_1") (pintype "passive"))
      (node (ref "R30") (pin "1") (pinfunction "1_1") (pintype "passive"))
    )
    (net (code "38") (name "Net-(IC4B-OUT)") (class "Default")
      (node (ref "IC4") (pin "7") (pinfunction "OUT_7") (pintype "output"))
      (node (ref "R22") (pin "2") (pinfunction "2_2") (pintype "passive"))
      (node (ref "R23") (pin "1") (pinfunction "1_1") (pintype "passive"))
      (node (ref "R24") (pin "1") (pinfunction "1_1") (pintype "passive"))
      (node (ref "R25") (pin "2") (pinfunction "2_2") (pintype "passive"))
    )
    (net (code "39") (name "Net-(IC5A-+IN)") (class "Default")
      (node (ref "IC5") (pin "3") (pinfunction "+IN_3") (pintype "input"))
      (node (ref "R39") (pin "2") (pinfunction "2_2") (pintype "passive"))
      (node (ref "R42") (pin "2") (pinfunction "2_2") (pintype "passive"))
    )
    (net (code "40") (name "Net-(IC5A--IN)") (class "Default")
      (node (ref "C16") (pin "1") (pinfunction "1_1") (pintype "passive"))
      (node (ref "IC5") (pin "2") (pinfunction "-IN_2") (pintype "input"))
      (node (ref "R43") (pin "1") (pinfunction "1_1") (pintype "passive"))
    )
    (net (code "41") (name "Net-(IC5A-OUT)") (class "Default")
      (node (ref "C16") (pin "2") (pinfunction "2_2") (pintype "passive"))
      (node (ref "IC5") (pin "1") (pinfunction "OUT_1") (pintype "output"))
      (node (ref "R41") (pin "2") (pinfunction "2_2") (pintype "passive"))
      (node (ref "R42") (pin "1") (pinfunction "1_1") (pintype "passive"))
      (node (ref "RATE") (pin "1") (pinfunction "1_1") (pintype "passive"))
    )
    (net (code "42") (name "Net-(IC5B-+IN)") (class "Default")
      (node (ref "IC5") (pin "5") (pinfunction "+IN_5") (pintype "input"))
      (node (ref "R35") (pin "2") (pinfunction "2_2") (pintype "passive"))
      (node (ref "R36") (pin "1") (pinfunction "1_1") (pintype "passive"))
    )
    (net (code "43") (name "Net-(IC5B--IN)") (class "Default")
      (node (ref "IC5") (pin "6") (pinfunction "-IN_6") (pintype "input"))
      (node (ref "R34") (pin "2") (pinfunction "2_2") (pintype "passive"))
    )
    (net (code "44") (name "Net-(IC5B-OUT)") (class "Default")
      (node (ref "IC5") (pin "7") (pinfunction "OUT_7") (pintype "output"))
      (node (ref "R32") (pin "1") (pinfunction "1_1") (pintype "passive"))
      (node (ref "R33") (pin "1") (pinfunction "1_1") (pintype "passive"))
      (node (ref "R36") (pin "2") (pinfunction "2_2") (pintype "passive"))
    )
    (net (code "45") (name "Net-(JP4-Pad1)") (class "Default")
      (node (ref "JP4") (pin "1") (pinfunction "1_1") (pintype "passive"))
      (node (ref "JP5") (pin "1") (pinfunction "1_1") (pintype "passive"))
      (node (ref "JP6") (pin "1") (pinfunction "1_1") (pintype "passive"))
    )
    (net (code "46") (name "Net-(JP14-Pad1)") (class "Default")
      (node (ref "JP14") (pin "1") (pinfunction "1_1") (pintype "passive"))
      (node (ref "JP15") (pin "1") (pinfunction "1_1") (pintype "passive"))
      (node (ref "JP19") (pin "1") (pinfunction "1_1") (pintype "passive"))
    )
    (net (code "47") (name "Net-(JP16-Pad1)") (class "Default")
      (node (ref "JP16") (pin "1") (pinfunction "1_1") (pintype "passive"))
      (node (ref "JP17") (pin "1") (pinfunction "1_1") (pintype "passive"))
      (node (ref "JP18") (pin "1") (pinfunction "1_1") (pintype "passive"))
    )
    (net (code "48") (name "Net-(JP20-Pad1)") (class "Default")
      (node (ref "JP20") (pin "1") (pinfunction "1_1") (pintype "passive"))
      (node (ref "JP21") (pin "1") (pinfunction "1_1") (pintype "passive"))
      (node (ref "JP25") (pin "1") (pinfunction "1_1") (pintype "passive"))
    )
    (net (code "49") (name "Net-(JP22-Pad1)") (class "Default")
      (node (ref "JP22") (pin "1") (pinfunction "1_1") (pintype "passive"))
      (node (ref "JP23") (pin "1") (pinfunction "1_1") (pintype "passive"))
      (node (ref "JP24") (pin "1") (pinfunction "1_1") (pintype "passive"))
    )
    (net (code "50") (name "Net-(JP26-Pad1)") (class "Default")
      (node (ref "JP26") (pin "1") (pinfunction "1_1") (pintype "passive"))
      (node (ref "JP27") (pin "1") (pinfunction "1_1") (pintype "passive"))
      (node (ref "JP31") (pin "1") (pinfunction "1_1") (pintype "passive"))
    )
    (net (code "51") (name "Net-(JP28-Pad1)") (class "Default")
      (node (ref "JP28") (pin "1") (pinfunction "1_1") (pintype "passive"))
      (node (ref "JP29") (pin "1") (pinfunction "1_1") (pintype "passive"))
      (node (ref "JP30") (pin "1") (pinfunction "1_1") (pintype "passive"))
    )
    (net (code "52") (name "Net-(JP32-Pad1)") (class "Default")
      (node (ref "JP32") (pin "1") (pinfunction "1_1") (pintype "passive"))
      (node (ref "JP33") (pin "1") (pinfunction "1_1") (pintype "passive"))
      (node (ref "JP34") (pin "1") (pinfunction "1_1") (pintype "passive"))
    )
    (net (code "53") (name "Net-(JP35-Pad1)") (class "Default")
      (node (ref "JP35") (pin "1") (pinfunction "1_1") (pintype "passive"))
      (node (ref "JP36") (pin "1") (pinfunction "1_1") (pintype "passive"))
      (node (ref "JP37") (pin "1") (pinfunction "1_1") (pintype "passive"))
    )
    (net (code "54") (name "Net-(JP38-Pad1)") (class "Default")
      (node (ref "JP38") (pin "1") (pinfunction "1_1") (pintype "passive"))
      (node (ref "JP39") (pin "1") (pinfunction "1_1") (pintype "passive"))
      (node (ref "JP40") (pin "1") (pinfunction "1_1") (pintype "passive"))
    )
    (net (code "55") (name "Net-(JP41-Pad1)") (class "Default")
      (node (ref "JP41") (pin "1") (pinfunction "1_1") (pintype "passive"))
      (node (ref "JP42") (pin "1") (pinfunction "1_1") (pintype "passive"))
      (node (ref "JP43") (pin "1") (pinfunction "1_1") (pintype "passive"))
    )
    (net (code "56") (name "Net-(JP53-Pad1)") (class "Default")
      (node (ref "JP53") (pin "1") (pinfunction "1_1") (pintype "passive"))
      (node (ref "JP54") (pin "1") (pinfunction "1_1") (pintype "passive"))
      (node (ref "JP55") (pin "1") (pinfunction "1_1") (pintype "passive"))
    )
    (net (code "57") (name "Net-(JP56-Pad1)") (class "Default")
      (node (ref "JP56") (pin "1") (pinfunction "1_1") (pintype "passive"))
      (node (ref "JP57") (pin "1") (pinfunction "1_1") (pintype "passive"))
      (node (ref "JP61") (pin "1") (pinfunction "1_1") (pintype "passive"))
    )
    (net (code "58") (name "Net-(JP62-Pad1)") (class "Default")
      (node (ref "JP62") (pin "1") (pinfunction "1_1") (pintype "passive"))
      (node (ref "JP63") (pin "1") (pinfunction "1_1") (pintype "passive"))
      (node (ref "JP67") (pin "1") (pinfunction "1_1") (pintype "passive"))
    )
    (net (code "59") (name "Net-(JP64-Pad1)") (class "Default")
      (node (ref "JP64") (pin "1") (pinfunction "1_1") (pintype "passive"))
      (node (ref "JP65") (pin "1") (pinfunction "1_1") (pintype "passive"))
      (node (ref "JP66") (pin "1") (pinfunction "1_1") (pintype "passive"))
    )
    (net (code "60") (name "Net-(JP68-Pad1)") (class "Default")
      (node (ref "JP68") (pin "1") (pinfunction "1_1") (pintype "passive"))
      (node (ref "JP69") (pin "1") (pinfunction "1_1") (pintype "passive"))
      (node (ref "JP73") (pin "1") (pinfunction "1_1") (pintype "passive"))
    )
    (net (code "61") (name "Net-(JP70-Pad1)") (class "Default")
      (node (ref "JP70") (pin "1") (pinfunction "1_1") (pintype "passive"))
      (node (ref "JP71") (pin "1") (pinfunction "1_1") (pintype "passive"))
      (node (ref "JP72") (pin "1") (pinfunction "1_1") (pintype "passive"))
    )
    (net (code "62") (name "Net-(JP74-Pad1)") (class "Default")
      (node (ref "JP74") (pin "1") (pinfunction "1_1") (pintype "passive"))
      (node (ref "JP75") (pin "1") (pinfunction "1_1") (pintype "passive"))
      (node (ref "JP76") (pin "1") (pinfunction "1_1") (pintype "passive"))
    )
    (net (code "63") (name "Net-(JP77-Pad1)") (class "Default")
      (node (ref "JP77") (pin "1") (pinfunction "1_1") (pintype "passive"))
      (node (ref "JP78") (pin "1") (pinfunction "1_1") (pintype "passive"))
      (node (ref "JP79") (pin "1") (pinfunction "1_1") (pintype "passive"))
    )
    (net (code "64") (name "Net-(JP82-Pad1)") (class "Default")
      (node (ref "JP82") (pin "1") (pinfunction "1_1") (pintype "passive"))
      (node (ref "JP83") (pin "1") (pinfunction "1_1") (pintype "passive"))
      (node (ref "JP89") (pin "1") (pinfunction "1_1") (pintype "passive"))
    )
    (net (code "65") (name "Net-(JP84-Pad1)") (class "Default")
      (node (ref "JP84") (pin "1") (pinfunction "1_1") (pintype "passive"))
      (node (ref "JP88") (pin "1") (pinfunction "1_1") (pintype "passive"))
      (node (ref "JP92") (pin "1") (pinfunction "1_1") (pintype "passive"))
    )
    (net (code "66") (name "Net-(JP85-Pad1)") (class "Default")
      (node (ref "JP85") (pin "1") (pinfunction "1_1") (pintype "passive"))
      (node (ref "JP86") (pin "1") (pinfunction "1_1") (pintype "passive"))
      (node (ref "JP87") (pin "1") (pinfunction "1_1") (pintype "passive"))
    )
    (net (code "67") (name "Net-(JP100-Pad1)") (class "Default")
      (node (ref "JP100") (pin "1") (pinfunction "1_1") (pintype "passive"))
      (node (ref "JP104") (pin "1") (pinfunction "1_1") (pintype "passive"))
      (node (ref "JP96") (pin "1") (pinfunction "1_1") (pintype "passive"))
    )
    (net (code "68") (name "Net-(JP101-Pad1)") (class "Default")
      (node (ref "JP101") (pin "1") (pinfunction "1_1") (pintype "passive"))
      (node (ref "JP102") (pin "1") (pinfunction "1_1") (pintype "passive"))
      (node (ref "JP103") (pin "1") (pinfunction "1_1") (pintype "passive"))
    )
    (net (code "69") (name "Net-(JP105-Pad1)") (class "Default")
      (node (ref "JP105") (pin "1") (pinfunction "1_1") (pintype "passive"))
      (node (ref "JP98") (pin "1") (pinfunction "1_1") (pintype "passive"))
      (node (ref "JP99") (pin "1") (pinfunction "1_1") (pintype "passive"))
    )
    (net (code "70") (name "Net-(JP106-Pad1)") (class "Default")
      (node (ref "JP106") (pin "1") (pinfunction "1_1") (pintype "passive"))
      (node (ref "JP107") (pin "1") (pinfunction "1_1") (pintype "passive"))
      (node (ref "JP113") (pin "1") (pinfunction "1_1") (pintype "passive"))
    )
    (net (code "71") (name "Net-(JP108-Pad1)") (class "Default")
      (node (ref "JP108") (pin "1") (pinfunction "1_1") (pintype "passive"))
      (node (ref "JP112") (pin "1") (pinfunction "1_1") (pintype "passive"))
      (node (ref "JP116") (pin "1") (pinfunction "1_1") (pintype "passive"))
    )
    (net (code "72") (name "Net-(JP109-Pad1)") (class "Default")
      (node (ref "JP109") (pin "1") (pinfunction "1_1") (pintype "passive"))
      (node (ref "JP110") (pin "1") (pinfunction "1_1") (pintype "passive"))
      (node (ref "JP111") (pin "1") (pinfunction "1_1") (pintype "passive"))
    )
    (net (code "73") (name "Net-(JP114-Pad1)") (class "Default")
      (node (ref "JP114") (pin "1") (pinfunction "1_1") (pintype "passive"))
      (node (ref "JP115") (pin "1") (pinfunction "1_1") (pintype "passive"))
      (node (ref "JP121") (pin "1") (pinfunction "1_1") (pintype "passive"))
    )
    (net (code "74") (name "Net-(JP117-Pad1)") (class "Default")
      (node (ref "JP117") (pin "1") (pinfunction "1_1") (pintype "passive"))
      (node (ref "JP118") (pin "1") (pinfunction "1_1") (pintype "passive"))
      (node (ref "JP119") (pin "1") (pinfunction "1_1") (pintype "passive"))
    )
    (net (code "75") (name "Net-(JP120-Pad1)") (class "Default")
      (node (ref "JP120") (pin "1") (pinfunction "1_1") (pintype "passive"))
      (node (ref "JP122") (pin "1") (pinfunction "1_1") (pintype "passive"))
      (node (ref "JP123") (pin "1") (pinfunction "1_1") (pintype "passive"))
    )
    (net (code "76") (name "Net-(JP124-Pad1)") (class "Default")
      (node (ref "JP124") (pin "1") (pinfunction "1_1") (pintype "passive"))
      (node (ref "JP125") (pin "1") (pinfunction "1_1") (pintype "passive"))
      (node (ref "JP126") (pin "1") (pinfunction "1_1") (pintype "passive"))
    )
    (net (code "77") (name "Net-(JP127-Pad1)") (class "Default")
      (node (ref "JP127") (pin "1") (pinfunction "1_1") (pintype "passive"))
      (node (ref "JP128") (pin "1") (pinfunction "1_1") (pintype "passive"))
      (node (ref "JP132") (pin "1") (pinfunction "1_1") (pintype "passive"))
    )
    (net (code "78") (name "Net-(JP129-Pad1)") (class "Default")
      (node (ref "JP129") (pin "1") (pinfunction "1_1") (pintype "passive"))
      (node (ref "JP130") (pin "1") (pinfunction "1_1") (pintype "passive"))
      (node (ref "JP131") (pin "1") (pinfunction "1_1") (pintype "passive"))
    )
    (net (code "79") (name "Net-(JP133-Pad1)") (class "Default")
      (node (ref "JP133") (pin "1") (pinfunction "1_1") (pintype "passive"))
      (node (ref "JP134") (pin "1") (pinfunction "1_1") (pintype "passive"))
      (node (ref "JP135") (pin "1") (pinfunction "1_1") (pintype "passive"))
    )
    (net (code "80") (name "Net-(JP136-Pad1)") (class "Default")
      (node (ref "JP136") (pin "1") (pinfunction "1_1") (pintype "passive"))
      (node (ref "JP80") (pin "1") (pinfunction "1_1") (pintype "passive"))
      (node (ref "JP81") (pin "1") (pinfunction "1_1") (pintype "passive"))
    )
    (net (code "81") (name "Net-(PITCH-Pad1)") (class "Default")
      (node (ref "PITCH") (pin "1") (pinfunction "1_1") (pintype "passive"))
      (node (ref "R21") (pin "1") (pinfunction "1_1") (pintype "passive"))
    )
    (net (code "82") (name "Net-(PITCH-Pad2)") (class "Default")
      (node (ref "PITCH") (pin "2") (pinfunction "2_2") (pintype "passive"))
      (node (ref "R18") (pin "1") (pinfunction "1_1") (pintype "passive"))
    )
    (net (code "83") (name "Net-(PWR-C)") (class "Default")
      (node (ref "PWR") (pin "K") (pinfunction "C_K") (pintype "passive"))
      (node (ref "R44") (pin "2") (pinfunction "2_2") (pintype "passive"))
    )
    (net (code "84") (name "Net-(Q2-PadB)") (class "Default")
      (node (ref "Q2") (pin "B") (pinfunction "B_B") (pintype "passive"))
      (node (ref "R33") (pin "2") (pinfunction "2_2") (pintype "passive"))
    )
    (net (code "85") (name "Net-(Q2-PadC)") (class "Default")
      (node (ref "Q2") (pin "C") (pinfunction "C_C") (pintype "passive"))
      (node (ref "R29") (pin "1") (pinfunction "1_1") (pintype "passive"))
    )
    (net (code "86") (name "Net-(Q3-B)") (class "Default")
      (node (ref "Q3") (pin "1") (pinfunction "C_1") (pintype "passive"))
      (node (ref "Q3") (pin "2") (pinfunction "B_2") (pintype "passive"))
      (node (ref "Q4") (pin "2") (pinfunction "B_2") (pintype "passive"))
      (node (ref "Q5") (pin "1") (pinfunction "C_1") (pintype "passive"))
    )
    (net (code "87") (name "Net-(Q4-C)") (class "Default")
      (node (ref "IC6") (pin "4") (pinfunction "4_4") (pintype "passive"))
      (node (ref "Q4") (pin "1") (pinfunction "C_1") (pintype "passive"))
    )
    (net (code "88") (name "Net-(R20-Pad1)") (class "Default")
      (node (ref "R20") (pin "1") (pinfunction "1_1") (pintype "passive"))
      (node (ref "SWEEP") (pin "3") (pinfunction "3_3") (pintype "passive"))
    )
    (net (code "89") (name "Net-(R26-Pad2)") (class "Default")
      (node (ref "R26") (pin "2") (pinfunction "2_2") (pintype "passive"))
      (node (ref "SWEEP") (pin "2") (pinfunction "2_2") (pintype "passive"))
    )
    (net (code "90") (name "Net-(R27-Pad2)") (class "Default")
      (node (ref "R27") (pin "2") (pinfunction "2_2") (pintype "passive"))
      (node (ref "SWEEP") (pin "4") (pinfunction "4_4") (pintype "passive"))
    )
    (net (code "91") (name "Net-(R31-Pad2)") (class "Default")
      (node (ref "R31") (pin "2") (pinfunction "2_2") (pintype "passive"))
      (node (ref "WAVE") (pin "1") (pinfunction "1_1") (pintype "passive"))
    )
    (net (code "92") (name "Net-(R32-Pad2)") (class "Default")
      (node (ref "R32") (pin "2") (pinfunction "2_2") (pintype "passive"))
      (node (ref "WAVE") (pin "3") (pinfunction "3_3") (pintype "passive"))
    )
    (net (code "93") (name "Net-(R37-Pad1)") (class "Default")
      (node (ref "R37") (pin "1") (pinfunction "1_1") (pintype "passive"))
      (node (ref "RATE") (pin "3") (pinfunction "3_3") (pintype "passive"))
    )
    (net (code "94") (name "Net-(R38-Pad2)") (class "Default")
      (node (ref "R38") (pin "2") (pinfunction "2_2") (pintype "passive"))
      (node (ref "RATE") (pin "2") (pinfunction "2_2") (pintype "passive"))
    )
    (net (code "95") (name "Net-(SENS-Pad1)") (class "Default")
      (node (ref "SENS") (pin "1") (pinfunction "1_1") (pintype "passive"))
      (node (ref "TRIG") (pin "2") (pinfunction "2_2") (pintype "passive"))
    )
    (net (code "96") (name "VCC") (class "Default")
      (node (ref "C10") (pin "+") (pinfunction "+_+") (pintype "passive"))
      (node (ref "C14") (pin "+") (pinfunction "+_+") (pintype "passive"))
      (node (ref "D1") (pin "C") (pinfunction "C_C") (pintype "passive"))
      (node (ref "IC1") (pin "8") (pinfunction "V+_8") (pintype "power_in"))
      (node (ref "IC3") (pin "8") (pinfunction "V+_8") (pintype "power_in"))
      (node (ref "IC4") (pin "8") (pinfunction "V+_8") (pintype "power_in"))
      (node (ref "IC5") (pin "8") (pinfunction "V+_8") (pintype "power_in"))
      (node (ref "IC6") (pin "9") (pinfunction "9_9") (pintype "passive"))
      (node (ref "JP143") (pin "1") (pinfunction "1_1") (pintype "passive"))
      (node (ref "JP144") (pin "1") (pinfunction "1_1") (pintype "passive"))
      (node (ref "JP145") (pin "1") (pinfunction "1_1") (pintype "passive"))
      (node (ref "JP2") (pin "1") (pinfunction "1_1") (pintype "passive"))
      (node (ref "JP3") (pin "1") (pinfunction "1_1") (pintype "passive"))
      (node (ref "JP44") (pin "1") (pinfunction "1_1") (pintype "passive"))
      (node (ref "JP45") (pin "1") (pinfunction "1_1") (pintype "passive"))
      (node (ref "JP46") (pin "1") (pinfunction "1_1") (pintype "passive"))
      (node (ref "JP58") (pin "1") (pinfunction "1_1") (pintype "passive"))
      (node (ref "JP59") (pin "1") (pinfunction "1_1") (pintype "passive"))
      (node (ref "JP60") (pin "1") (pinfunction "1_1") (pintype "passive"))
      (node (ref "JP7") (pin "1") (pinfunction "1_1") (pintype "passive"))
      (node (ref "PWR") (pin "A") (pinfunction "A_A") (pintype "passive"))
      (node (ref "Q3") (pin "3") (pinfunction "E_3") (pintype "passive"))
      (node (ref "Q4") (pin "3") (pinfunction "E_3") (pintype "passive"))
      (node (ref "R10") (pin "2") (pinfunction "2_2") (pintype "passive"))
      (node (ref "R18") (pin "2") (pinfunction "2_2") (pintype "passive"))
      (node (ref "R2") (pin "1") (pinfunction "1_1") (pintype "passive"))
    )
    (net (code "97") (name "unconnected-(IC6-Pad3)") (class "Default")
      (node (ref "IC6") (pin "3") (pinfunction "3_3") (pintype "passive"))
    )
  )
)
